# VisualOutput.net
KiCad netlist of a schematic drawn in Altium Designer
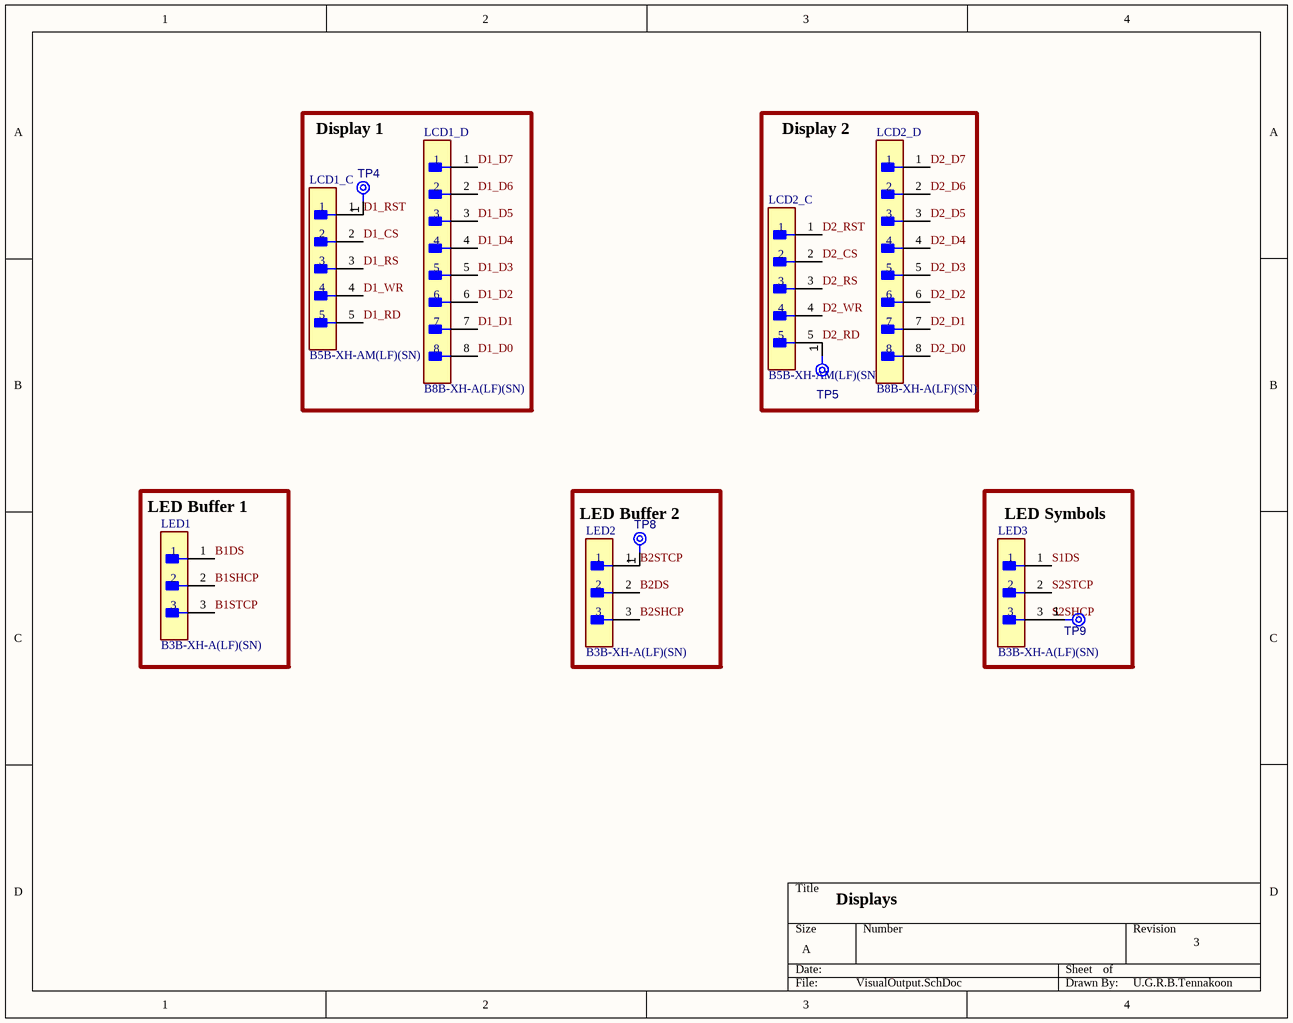
[diagram p0: VisualOutput.SchDoc]

(export (version "E")
  (design (tool "Eeschema 10.0.6"))
  (components
    (comp (ref "LCD1_C")
      (value "B5B-XH-AM(LF)(SN)")
      (footprint "FP-B5B-XH-AM_LF_SN-MFG")
      (description "CONN HEADER VERT 5POS 2.5MM")
      (libsource (lib "Altium Content Vault") (part "bf93c07fd2649a848d0ec8585582aab"))
    )
    (comp (ref "LCD1_D")
      (value "B8B-XH-A(LF)(SN)")
      (footprint "FP-B8B-XH-A_LF_SN-MFG")
      (description "CONN HEADER VERT 8POS 2.5MM")
      (libsource (lib "Altium Content Vault") (part "99ec2b232beb5d2356d4d77f6a047f0"))
    )
    (comp (ref "LCD2_C")
      (value "B5B-XH-AM(LF)(SN)")
      (footprint "FP-B5B-XH-AM_LF_SN-MFG")
      (description "CONN HEADER VERT 5POS 2.5MM")
      (libsource (lib "Altium Content Vault") (part "bf93c07fd2649a848d0ec8585582aab"))
    )
    (comp (ref "LCD2_D")
      (value "B8B-XH-A(LF)(SN)")
      (footprint "FP-B8B-XH-A_LF_SN-MFG")
      (description "CONN HEADER VERT 8POS 2.5MM")
      (libsource (lib "Altium Content Vault") (part "99ec2b232beb5d2356d4d77f6a047f0"))
    )
    (comp (ref "LED1")
      (value "B3B-XH-A(LF)(SN)")
      (footprint "FP-B3B-XH-A_LF_SN-MFG")
      (description "CONN HEADER VERT 3POS 2.5MM")
      (libsource (lib "Altium Content Vault") (part "0d3f023dd272f625e17a2be33dea85f"))
    )
    (comp (ref "LED2")
      (value "B3B-XH-A(LF)(SN)")
      (footprint "FP-B3B-XH-A_LF_SN-MFG")
      (description "CONN HEADER VERT 3POS 2.5MM")
      (libsource (lib "Altium Content Vault") (part "0d3f023dd272f625e17a2be33dea85f"))
    )
    (comp (ref "LED3")
      (value "B3B-XH-A(LF)(SN)")
      (footprint "FP-B3B-XH-A_LF_SN-MFG")
      (description "CONN HEADER VERT 3POS 2.5MM")
      (libsource (lib "Altium Content Vault") (part "0d3f023dd272f625e17a2be33dea85f"))
    )
    (comp (ref "TP4")
      (value "TPAD6R")
      (footprint "TP06R")
      (description "0.6mm round")
      (libsource (lib "ravindu tennakoon") (part "CMP-001-0001-4"))
    )
    (comp (ref "TP5")
      (value "TPAD6R")
      (footprint "TP06R")
      (description "0.6mm round")
      (libsource (lib "ravindu tennakoon") (part "CMP-001-0001-4"))
    )
    (comp (ref "TP8")
      (value "TPAD6R")
      (footprint "TP06R")
      (description "0.6mm round")
      (libsource (lib "ravindu tennakoon") (part "CMP-001-0001-4"))
    )
    (comp (ref "TP9")
      (value "TPAD6R")
      (footprint "TP06R")
      (description "0.6mm round")
      (libsource (lib "ravindu tennakoon") (part "CMP-001-0001-4"))
    )
  )
  (nets
    (net (code "1") (name "/B1DS") (class "Default")
      (node (ref "LED1") (pin "1") (pinfunction "1_1") (pintype "passive"))
    )
    (net (code "2") (name "/B1SHCP") (class "Default")
      (node (ref "LED1") (pin "2") (pinfunction "2_2") (pintype "passive"))
    )
    (net (code "3") (name "/B1STCP") (class "Default")
      (node (ref "LED1") (pin "3") (pinfunction "3_3") (pintype "passive"))
    )
    (net (code "4") (name "/B2DS") (class "Default")
      (node (ref "LED2") (pin "2") (pinfunction "2_2") (pintype "passive"))
    )
    (net (code "5") (name "/B2SHCP") (class "Default")
      (node (ref "LED2") (pin "3") (pinfunction "3_3") (pintype "passive"))
    )
    (net (code "6") (name "/B2STCP") (class "Default")
      (node (ref "LED2") (pin "1") (pinfunction "1_1") (pintype "passive"))
      (node (ref "TP8") (pin "1") (pinfunction "TP_1") (pintype "passive"))
    )
    (net (code "7") (name "/D1_CS") (class "Default")
      (node (ref "LCD1_C") (pin "2") (pinfunction "2_2") (pintype "passive"))
    )
    (net (code "8") (name "/D1_D0") (class "Default")
      (node (ref "LCD1_D") (pin "8") (pinfunction "8_8") (pintype "passive"))
    )
    (net (code "9") (name "/D1_D1") (class "Default")
      (node (ref "LCD1_D") (pin "7") (pinfunction "7_7") (pintype "passive"))
    )
    (net (code "10") (name "/D1_D2") (class "Default")
      (node (ref "LCD1_D") (pin "6") (pinfunction "6_6") (pintype "passive"))
    )
    (net (code "11") (name "/D1_D3") (class "Default")
      (node (ref "LCD1_D") (pin "5") (pinfunction "5_5") (pintype "passive"))
    )
    (net (code "12") (name "/D1_D4") (class "Default")
      (node (ref "LCD1_D") (pin "4") (pinfunction "4_4") (pintype "passive"))
    )
    (net (code "13") (name "/D1_D5") (class "Default")
      (node (ref "LCD1_D") (pin "3") (pinfunction "3_3") (pintype "passive"))
    )
    (net (code "14") (name "/D1_D6") (class "Default")
      (node (ref "LCD1_D") (pin "2") (pinfunction "2_2") (pintype "passive"))
    )
    (net (code "15") (name "/D1_D7") (class "Default")
      (node (ref "LCD1_D") (pin "1") (pinfunction "1_1") (pintype "passive"))
    )
    (net (code "16") (name "/D1_RD") (class "Default")
      (node (ref "LCD1_C") (pin "5") (pinfunction "5_5") (pintype "passive"))
    )
    (net (code "17") (name "/D1_RS") (class "Default")
      (node (ref "LCD1_C") (pin "3") (pinfunction "3_3") (pintype "passive"))
    )
    (net (code "18") (name "/D1_RST") (class "Default")
      (node (ref "LCD1_C") (pin "1") (pinfunction "1_1") (pintype "passive"))
      (node (ref "TP4") (pin "1") (pinfunction "TP_1") (pintype "passive"))
    )
    (net (code "19") (name "/D1_WR") (class "Default")
      (node (ref "LCD1_C") (pin "4") (pinfunction "4_4") (pintype "passive"))
    )
    (net (code "20") (name "/D2_CS") (class "Default")
      (node (ref "LCD2_C") (pin "2") (pinfunction "2_2") (pintype "passive"))
    )
    (net (code "21") (name "/D2_D0") (class "Default")
      (node (ref "LCD2_D") (pin "8") (pinfunction "8_8") (pintype "passive"))
    )
    (net (code "22") (name "/D2_D1") (class "Default")
      (node (ref "LCD2_D") (pin "7") (pinfunction "7_7") (pintype "passive"))
    )
    (net (code "23") (name "/D2_D2") (class "Default")
      (node (ref "LCD2_D") (pin "6") (pinfunction "6_6") (pintype "passive"))
    )
    (net (code "24") (name "/D2_D3") (class "Default")
      (node (ref "LCD2_D") (pin "5") (pinfunction "5_5") (pintype "passive"))
    )
    (net (code "25") (name "/D2_D4") (class "Default")
      (node (ref "LCD2_D") (pin "4") (pinfunction "4_4") (pintype "passive"))
    )
    (net (code "26") (name "/D2_D5") (class "Default")
      (node (ref "LCD2_D") (pin "3") (pinfunction "3_3") (pintype "passive"))
    )
    (net (code "27") (name "/D2_D6") (class "Default")
      (node (ref "LCD2_D") (pin "2") (pinfunction "2_2") (pintype "passive"))
    )
    (net (code "28") (name "/D2_D7") (class "Default")
      (node (ref "LCD2_D") (pin "1") (pinfunction "1_1") (pintype "passive"))
    )
    (net (code "29") (name "/D2_RD") (class "Default")
      (node (ref "LCD2_C") (pin "5") (pinfunction "5_5") (pintype "passive"))
      (node (ref "TP5") (pin "1") (pinfunction "TP_1") (pintype "passive"))
    )
    (net (code "30") (name "/D2_RS") (class "Default")
      (node (ref "LCD2_C") (pin "3") (pinfunction "3_3") (pintype "passive"))
    )
    (net (code "31") (name "/D2_RST") (class "Default")
      (node (ref "LCD2_C") (pin "1") (pinfunction "1_1") (pintype "passive"))
    )
    (net (code "32") (name "/D2_WR") (class "Default")
      (node (ref "LCD2_C") (pin "4") (pinfunction "4_4") (pintype "passive"))
    )
    (net (code "33") (name "/S1DS") (class "Default")
      (node (ref "LED3") (pin "1") (pinfunction "1_1") (pintype "passive"))
    )
    (net (code "34") (name "/S2SHCP") (class "Default")
      (node (ref "LED3") (pin "3") (pinfunction "3_3") (pintype "passive"))
      (node (ref "TP9") (pin "1") (pinfunction "TP_1") (pintype "passive"))
    )
    (net (code "35") (name "/S2STCP") (class "Default")
      (node (ref "LED3") (pin "2") (pinfunction "2_2") (pintype "passive"))
    )
  )
)
